# TEENSY_1.net
KiCad netlist of a schematic drawn in Altium Designer
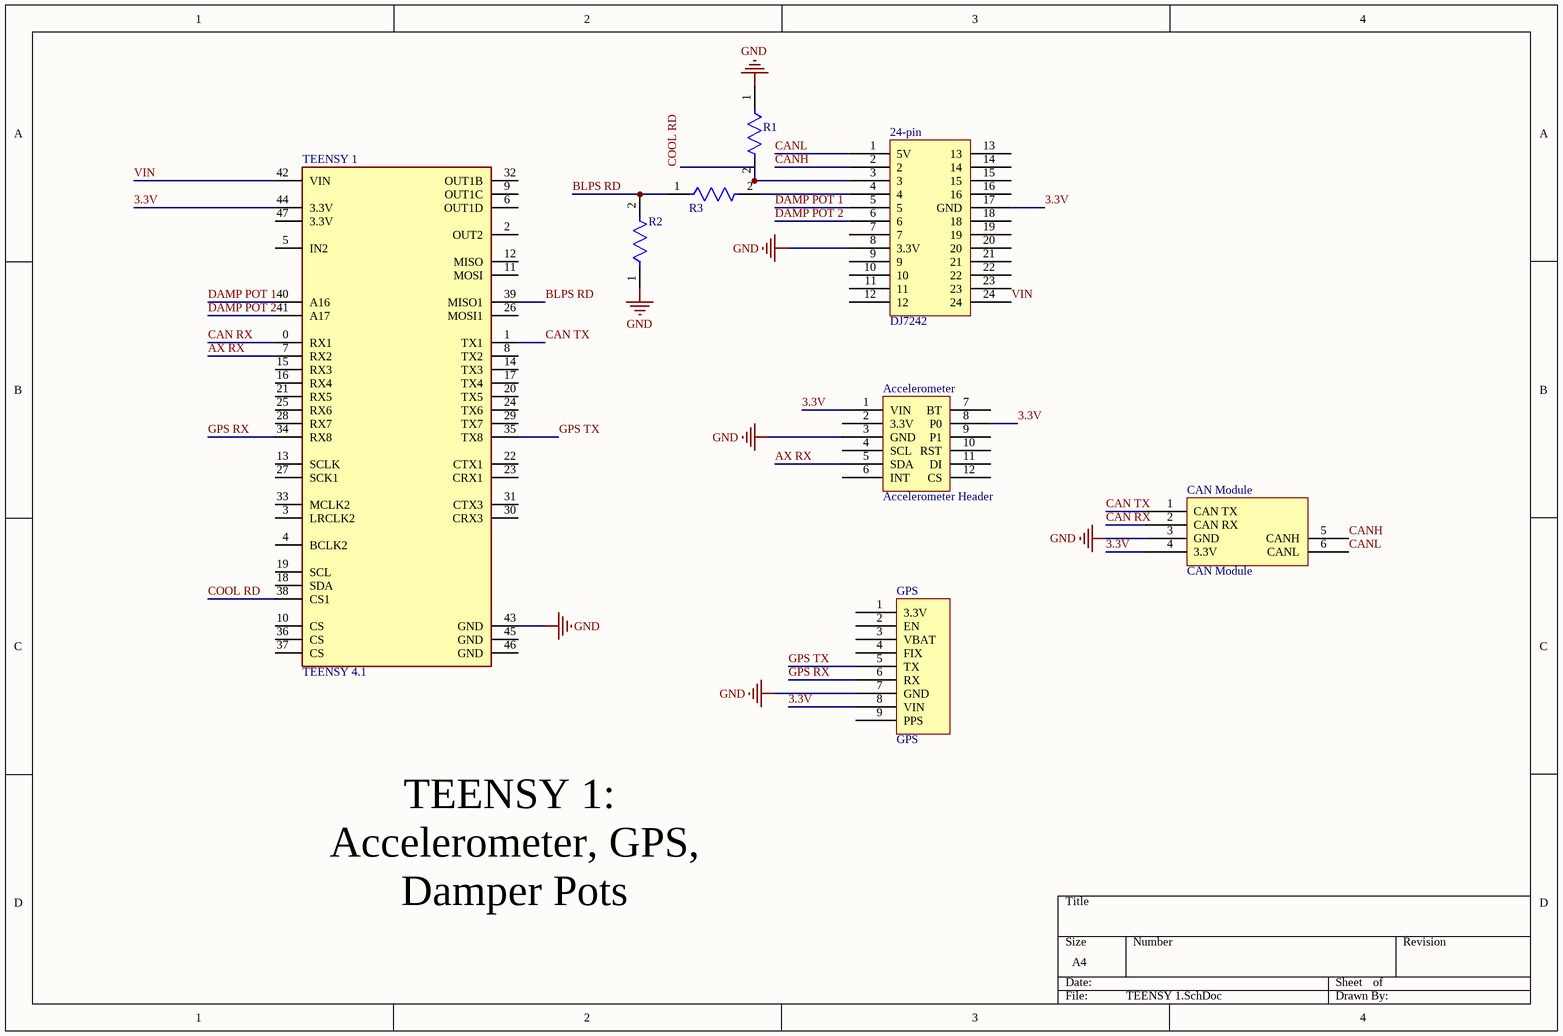
[diagram p0: TEENSY 1.SchDoc]

(export (version "E")
  (design (tool "Eeschema 10.0.6"))
  (components
    (comp (ref "24-pin")
      (value "DJ7242")
      (footprint "DJ7242-Footprint-1")
      (description "24-pin connector")
      (libsource (lib "cmabey15") (part "DJ7242-Symbol-1"))
    )
    (comp (ref "Accelerometer")
      (value "Accelerometer Header")
      (footprint "Accelerometer Header-Footprint-1")
      (description "Header for Adafruit Accelerometer")
      (libsource (lib "cmabey15") (part "Accel"))
    )
    (comp (ref "CAN Module")
      (value "CAN Module")
      (footprint "CAN Module-Footprint-1")
      (description "CAN waveshare")
      (libsource (lib "cmabey15") (part "CAN Module-Symbol-1"))
    )
    (comp (ref "GPS")
      (value "GPS")
      (footprint "GPS-Footprint-1")
      (description "Adafruit GPS chip")
      (libsource (lib "cmabey15") (part "GPS"))
    )
    (comp (ref "R1")
      (value "CMF5073K200FHEB")
      (footprint "FP-CMF50-0")
      (description "CMF5073K200FHEB Res Metal Film 73.2K Ohm 1% 0.125W(1/8W) ±50ppm/°C Epoxy AXL T/R")
      (fields (field (name "TOLERANCE") "1%"))
      (libsource (lib "Altium Content Vault") (part "1029c3af85768c4190bb7ad29bc67b5"))
    )
    (comp (ref "R2")
      (value "CMF5073K200FHEB")
      (footprint "FP-CMF50-0")
      (description "CMF5073K200FHEB Res Metal Film 73.2K Ohm 1% 0.125W(1/8W) ±50ppm/°C Epoxy AXL T/R")
      (fields (field (name "TOLERANCE") "1%"))
      (libsource (lib "Altium Content Vault") (part "1029c3af85768c4190bb7ad29bc67b5"))
    )
    (comp (ref "R3")
      (value "CMF5073K200FHEB")
      (footprint "FP-CMF50-0")
      (description "CMF5073K200FHEB Res Metal Film 73.2K Ohm 1% 0.125W(1/8W) ±50ppm/°C Epoxy AXL T/R")
      (fields (field (name "TOLERANCE") "1%"))
      (libsource (lib "Altium Content Vault") (part "1029c3af85768c4190bb7ad29bc67b5"))
    )
    (comp (ref "TEENSY 1")
      (value "TEENSY 4.1")
      (footprint "FP-DEV-16996-MFG")
      (description "TEENSY 4.1 (HEADERS)")
      (libsource (lib "Altium Content Vault") (part "080115a1ce54750370cf87ec145ee29"))
    )
  )
  (nets
    (net (code "1") (name "/3.3V") (class "Default")
      (node (ref "24-pin") (pin "17") (pinfunction "GND_17") (pintype "passive"))
      (node (ref "Accelerometer") (pin "1") (pinfunction "VIN_1") (pintype "passive"))
      (node (ref "Accelerometer") (pin "8") (pinfunction "P0_8") (pintype "passive"))
      (node (ref "CAN Module") (pin "4") (pinfunction "3.3V_4") (pintype "passive"))
      (node (ref "GPS") (pin "8") (pinfunction "VIN_8") (pintype "passive"))
      (node (ref "TEENSY 1") (pin "44") (pinfunction "3.3V_44") (pintype "passive"))
    )
    (net (code "2") (name "/AX RX") (class "Default")
      (node (ref "Accelerometer") (pin "5") (pinfunction "SDA_5") (pintype "passive"))
      (node (ref "TEENSY 1") (pin "7") (pinfunction "RX2_7") (pintype "passive"))
    )
    (net (code "3") (name "/BLPS RD") (class "Default")
      (node (ref "R2") (pin "2") (pinfunction "2_2") (pintype "passive"))
      (node (ref "R3") (pin "1") (pinfunction "1_1") (pintype "passive"))
      (node (ref "TEENSY 1") (pin "39") (pinfunction "MISO1_39") (pintype "passive"))
    )
    (net (code "4") (name "/CAN RX") (class "Default")
      (node (ref "CAN Module") (pin "2") (pinfunction "CAN_RX_2") (pintype "passive"))
      (node (ref "TEENSY 1") (pin "0") (pinfunction "RX1_0") (pintype "passive"))
    )
    (net (code "5") (name "/CAN TX") (class "Default")
      (node (ref "CAN Module") (pin "1") (pinfunction "CAN_TX_1") (pintype "passive"))
      (node (ref "TEENSY 1") (pin "1") (pinfunction "TX1_1") (pintype "passive"))
    )
    (net (code "6") (name "/CANH") (class "Default")
      (node (ref "24-pin") (pin "2") (pinfunction "2_2") (pintype "passive"))
      (node (ref "CAN Module") (pin "5") (pinfunction "CANH_5") (pintype "passive"))
    )
    (net (code "7") (name "/CANL") (class "Default")
      (node (ref "24-pin") (pin "1") (pinfunction "5V_1") (pintype "passive"))
      (node (ref "CAN Module") (pin "6") (pinfunction "CANL_6") (pintype "passive"))
    )
    (net (code "8") (name "/COOL RD") (class "Default")
      (node (ref "24-pin") (pin "3") (pinfunction "3_3") (pintype "passive"))
      (node (ref "R1") (pin "2") (pinfunction "2_2") (pintype "passive"))
      (node (ref "TEENSY 1") (pin "38") (pinfunction "CS1_38") (pintype "passive"))
    )
    (net (code "9") (name "/DAMP POT 1") (class "Default")
      (node (ref "24-pin") (pin "5") (pinfunction "5_5") (pintype "passive"))
      (node (ref "TEENSY 1") (pin "40") (pinfunction "A16_40") (pintype "passive"))
    )
    (net (code "10") (name "/DAMP POT 2") (class "Default")
      (node (ref "24-pin") (pin "6") (pinfunction "6_6") (pintype "passive"))
      (node (ref "TEENSY 1") (pin "41") (pinfunction "A17_41") (pintype "passive"))
    )
    (net (code "11") (name "/GPS RX") (class "Default")
      (node (ref "GPS") (pin "6") (pinfunction "RX_6") (pintype "passive"))
      (node (ref "TEENSY 1") (pin "34") (pinfunction "RX8_34") (pintype "passive"))
    )
    (net (code "12") (name "/GPS TX") (class "Default")
      (node (ref "GPS") (pin "5") (pinfunction "TX_5") (pintype "passive"))
      (node (ref "TEENSY 1") (pin "35") (pinfunction "TX8_35") (pintype "passive"))
    )
    (net (code "13") (name "/VIN") (class "Default")
      (node (ref "24-pin") (pin "24") (pinfunction "24_24") (pintype "passive"))
      (node (ref "TEENSY 1") (pin "42") (pinfunction "VIN_42") (pintype "passive"))
    )
    (net (code "14") (name "GND") (class "Default")
      (node (ref "24-pin") (pin "8") (pinfunction "3.3V_8") (pintype "passive"))
      (node (ref "Accelerometer") (pin "3") (pinfunction "GND_3") (pintype "passive"))
      (node (ref "CAN Module") (pin "3") (pinfunction "GND_3") (pintype "passive"))
      (node (ref "GPS") (pin "7") (pinfunction "GND_7") (pintype "passive"))
      (node (ref "R1") (pin "1") (pinfunction "1_1") (pintype "passive"))
      (node (ref "R2") (pin "1") (pinfunction "1_1") (pintype "passive"))
      (node (ref "TEENSY 1") (pin "43") (pinfunction "GND_43") (pintype "passive"))
    )
    (net (code "15") (name "Net-(24-pin-Pad4)") (class "Default")
      (node (ref "24-pin") (pin "4") (pinfunction "4_4") (pintype "passive"))
      (node (ref "R3") (pin "2") (pinfunction "2_2") (pintype "passive"))
    )
    (net (code "16") (name "unconnected-(24-pin-Pad7)") (class "Default")
      (node (ref "24-pin") (pin "7") (pinfunction "7_7") (pintype "passive"))
    )
    (net (code "17") (name "unconnected-(24-pin-Pad9)") (class "Default")
      (node (ref "24-pin") (pin "9") (pinfunction "9_9") (pintype "passive"))
    )
    (net (code "18") (name "unconnected-(24-pin-Pad10)") (class "Default")
      (node (ref "24-pin") (pin "10") (pinfunction "10_10") (pintype "passive"))
    )
    (net (code "19") (name "unconnected-(24-pin-Pad11)") (class "Default")
      (node (ref "24-pin") (pin "11") (pinfunction "11_11") (pintype "passive"))
    )
    (net (code "20") (name "unconnected-(24-pin-Pad12)") (class "Default")
      (node (ref "24-pin") (pin "12") (pinfunction "12_12") (pintype "passive"))
    )
    (net (code "21") (name "unconnected-(24-pin-Pad13)") (class "Default")
      (node (ref "24-pin") (pin "13") (pinfunction "13_13") (pintype "passive"))
    )
    (net (code "22") (name "unconnected-(24-pin-Pad14)") (class "Default")
      (node (ref "24-pin") (pin "14") (pinfunction "14_14") (pintype "passive"))
    )
    (net (code "23") (name "unconnected-(24-pin-Pad15)") (class "Default")
      (node (ref "24-pin") (pin "15") (pinfunction "15_15") (pintype "passive"))
    )
    (net (code "24") (name "unconnected-(24-pin-Pad16)") (class "Default")
      (node (ref "24-pin") (pin "16") (pinfunction "16_16") (pintype "passive"))
    )
    (net (code "25") (name "unconnected-(24-pin-Pad18)") (class "Default")
      (node (ref "24-pin") (pin "18") (pinfunction "18_18") (pintype "passive"))
    )
    (net (code "26") (name "unconnected-(24-pin-Pad19)") (class "Default")
      (node (ref "24-pin") (pin "19") (pinfunction "19_19") (pintype "passive"))
    )
    (net (code "27") (name "unconnected-(24-pin-Pad20)") (class "Default")
      (node (ref "24-pin") (pin "20") (pinfunction "20_20") (pintype "passive"))
    )
    (net (code "28") (name "unconnected-(24-pin-Pad21)") (class "Default")
      (node (ref "24-pin") (pin "21") (pinfunction "21_21") (pintype "passive"))
    )
    (net (code "29") (name "unconnected-(24-pin-Pad22)") (class "Default")
      (node (ref "24-pin") (pin "22") (pinfunction "22_22") (pintype "passive"))
    )
    (net (code "30") (name "unconnected-(24-pin-Pad23)") (class "Default")
      (node (ref "24-pin") (pin "23") (pinfunction "23_23") (pintype "passive"))
    )
    (net (code "31") (name "unconnected-(Accelerometer-3.3V-Pad2)") (class "Default")
      (node (ref "Accelerometer") (pin "2") (pinfunction "3.3V_2") (pintype "passive"))
    )
    (net (code "32") (name "unconnected-(Accelerometer-BT-Pad7)") (class "Default")
      (node (ref "Accelerometer") (pin "7") (pinfunction "BT_7") (pintype "passive"))
    )
    (net (code "33") (name "unconnected-(Accelerometer-CS-Pad12)") (class "Default")
      (node (ref "Accelerometer") (pin "12") (pinfunction "CS_12") (pintype "passive"))
    )
    (net (code "34") (name "unconnected-(Accelerometer-DI-Pad11)") (class "Default")
      (node (ref "Accelerometer") (pin "11") (pinfunction "DI_11") (pintype "passive"))
    )
    (net (code "35") (name "unconnected-(Accelerometer-INT-Pad6)") (class "Default")
      (node (ref "Accelerometer") (pin "6") (pinfunction "INT_6") (pintype "passive"))
    )
    (net (code "36") (name "unconnected-(Accelerometer-P1-Pad9)") (class "Default")
      (node (ref "Accelerometer") (pin "9") (pinfunction "P1_9") (pintype "passive"))
    )
    (net (code "37") (name "unconnected-(Accelerometer-RST-Pad10)") (class "Default")
      (node (ref "Accelerometer") (pin "10") (pinfunction "RST_10") (pintype "passive"))
    )
    (net (code "38") (name "unconnected-(Accelerometer-SCL-Pad4)") (class "Default")
      (node (ref "Accelerometer") (pin "4") (pinfunction "SCL_4") (pintype "passive"))
    )
    (net (code "39") (name "unconnected-(GPS-3.3V-Pad1)") (class "Default")
      (node (ref "GPS") (pin "1") (pinfunction "3.3V_1") (pintype "passive"))
    )
    (net (code "40") (name "unconnected-(GPS-EN-Pad2)") (class "Default")
      (node (ref "GPS") (pin "2") (pinfunction "EN_2") (pintype "passive"))
    )
    (net (code "41") (name "unconnected-(GPS-FIX-Pad4)") (class "Default")
      (node (ref "GPS") (pin "4") (pinfunction "FIX_4") (pintype "passive"))
    )
    (net (code "42") (name "unconnected-(GPS-PPS-Pad9)") (class "Default")
      (node (ref "GPS") (pin "9") (pinfunction "PPS_9") (pintype "passive"))
    )
    (net (code "43") (name "unconnected-(GPS-VBAT-Pad3)") (class "Default")
      (node (ref "GPS") (pin "3") (pinfunction "VBAT_3") (pintype "passive"))
    )
    (net (code "44") (name "unconnected-(TEENSY 1-3.3V-Pad47)") (class "Default")
      (node (ref "TEENSY 1") (pin "47") (pinfunction "3.3V_47") (pintype "passive"))
    )
    (net (code "45") (name "unconnected-(TEENSY 1-BCLK2-Pad4)") (class "Default")
      (node (ref "TEENSY 1") (pin "4") (pinfunction "BCLK2_4") (pintype "passive"))
    )
    (net (code "46") (name "unconnected-(TEENSY 1-CRX1-Pad23)") (class "Default")
      (node (ref "TEENSY 1") (pin "23") (pinfunction "CRX1_23") (pintype "passive"))
    )
    (net (code "47") (name "unconnected-(TEENSY 1-CRX3-Pad30)") (class "Default")
      (node (ref "TEENSY 1") (pin "30") (pinfunction "CRX3_30") (pintype "passive"))
    )
    (net (code "48") (name "unconnected-(TEENSY 1-CS-Pad10)") (class "Default")
      (node (ref "TEENSY 1") (pin "10") (pinfunction "CS_10") (pintype "passive"))
    )
    (net (code "49") (name "unconnected-(TEENSY 1-CS-Pad36)") (class "Default")
      (node (ref "TEENSY 1") (pin "36") (pinfunction "CS_36") (pintype "passive"))
    )
    (net (code "50") (name "unconnected-(TEENSY 1-CS-Pad37)") (class "Default")
      (node (ref "TEENSY 1") (pin "37") (pinfunction "CS_37") (pintype "passive"))
    )
    (net (code "51") (name "unconnected-(TEENSY 1-CTX1-Pad22)") (class "Default")
      (node (ref "TEENSY 1") (pin "22") (pinfunction "CTX1_22") (pintype "passive"))
    )
    (net (code "52") (name "unconnected-(TEENSY 1-CTX3-Pad31)") (class "Default")
      (node (ref "TEENSY 1") (pin "31") (pinfunction "CTX3_31") (pintype "passive"))
    )
    (net (code "53") (name "unconnected-(TEENSY 1-GND-Pad45)") (class "Default")
      (node (ref "TEENSY 1") (pin "45") (pinfunction "GND_45") (pintype "passive"))
    )
    (net (code "54") (name "unconnected-(TEENSY 1-GND-Pad46)") (class "Default")
      (node (ref "TEENSY 1") (pin "46") (pinfunction "GND_46") (pintype "passive"))
    )
    (net (code "55") (name "unconnected-(TEENSY 1-IN2-Pad5)") (class "Default")
      (node (ref "TEENSY 1") (pin "5") (pinfunction "IN2_5") (pintype "passive"))
    )
    (net (code "56") (name "unconnected-(TEENSY 1-LRCLK2-Pad3)") (class "Default")
      (node (ref "TEENSY 1") (pin "3") (pinfunction "LRCLK2_3") (pintype "passive"))
    )
    (net (code "57") (name "unconnected-(TEENSY 1-MCLK2-Pad33)") (class "Default")
      (node (ref "TEENSY 1") (pin "33") (pinfunction "MCLK2_33") (pintype "passive"))
    )
    (net (code "58") (name "unconnected-(TEENSY 1-MISO-Pad12)") (class "Default")
      (node (ref "TEENSY 1") (pin "12") (pinfunction "MISO_12") (pintype "passive"))
    )
    (net (code "59") (name "unconnected-(TEENSY 1-MOSI-Pad11)") (class "Default")
      (node (ref "TEENSY 1") (pin "11") (pinfunction "MOSI_11") (pintype "passive"))
    )
    (net (code "60") (name "unconnected-(TEENSY 1-MOSI1-Pad26)") (class "Default")
      (node (ref "TEENSY 1") (pin "26") (pinfunction "MOSI1_26") (pintype "passive"))
    )
    (net (code "61") (name "unconnected-(TEENSY 1-OUT1B-Pad32)") (class "Default")
      (node (ref "TEENSY 1") (pin "32") (pinfunction "OUT1B_32") (pintype "passive"))
    )
    (net (code "62") (name "unconnected-(TEENSY 1-OUT1C-Pad9)") (class "Default")
      (node (ref "TEENSY 1") (pin "9") (pinfunction "OUT1C_9") (pintype "passive"))
    )
    (net (code "63") (name "unconnected-(TEENSY 1-OUT1D-Pad6)") (class "Default")
      (node (ref "TEENSY 1") (pin "6") (pinfunction "OUT1D_6") (pintype "passive"))
    )
    (net (code "64") (name "unconnected-(TEENSY 1-OUT2-Pad2)") (class "Default")
      (node (ref "TEENSY 1") (pin "2") (pinfunction "OUT2_2") (pintype "passive"))
    )
    (net (code "65") (name "unconnected-(TEENSY 1-RX3-Pad15)") (class "Default")
      (node (ref "TEENSY 1") (pin "15") (pinfunction "RX3_15") (pintype "passive"))
    )
    (net (code "66") (name "unconnected-(TEENSY 1-RX4-Pad16)") (class "Default")
      (node (ref "TEENSY 1") (pin "16") (pinfunction "RX4_16") (pintype "passive"))
    )
    (net (code "67") (name "unconnected-(TEENSY 1-RX5-Pad21)") (class "Default")
      (node (ref "TEENSY 1") (pin "21") (pinfunction "RX5_21") (pintype "passive"))
    )
    (net (code "68") (name "unconnected-(TEENSY 1-RX6-Pad25)") (class "Default")
      (node (ref "TEENSY 1") (pin "25") (pinfunction "RX6_25") (pintype "passive"))
    )
    (net (code "69") (name "unconnected-(TEENSY 1-RX7-Pad28)") (class "Default")
      (node (ref "TEENSY 1") (pin "28") (pinfunction "RX7_28") (pintype "passive"))
    )
    (net (code "70") (name "unconnected-(TEENSY 1-SCK1-Pad27)") (class "Default")
      (node (ref "TEENSY 1") (pin "27") (pinfunction "SCK1_27") (pintype "passive"))
    )
    (net (code "71") (name "unconnected-(TEENSY 1-SCL-Pad19)") (class "Default")
      (node (ref "TEENSY 1") (pin "19") (pinfunction "SCL_19") (pintype "passive"))
    )
    (net (code "72") (name "unconnected-(TEENSY 1-SCLK-Pad13)") (class "Default")
      (node (ref "TEENSY 1") (pin "13") (pinfunction "SCLK_13") (pintype "passive"))
    )
    (net (code "73") (name "unconnected-(TEENSY 1-SDA-Pad18)") (class "Default")
      (node (ref "TEENSY 1") (pin "18") (pinfunction "SDA_18") (pintype "passive"))
    )
    (net (code "74") (name "unconnected-(TEENSY 1-TX2-Pad8)") (class "Default")
      (node (ref "TEENSY 1") (pin "8") (pinfunction "TX2_8") (pintype "passive"))
    )
    (net (code "75") (name "unconnected-(TEENSY 1-TX3-Pad14)") (class "Default")
      (node (ref "TEENSY 1") (pin "14") (pinfunction "TX3_14") (pintype "passive"))
    )
    (net (code "76") (name "unconnected-(TEENSY 1-TX4-Pad17)") (class "Default")
      (node (ref "TEENSY 1") (pin "17") (pinfunction "TX4_17") (pintype "passive"))
    )
    (net (code "77") (name "unconnected-(TEENSY 1-TX5-Pad20)") (class "Default")
      (node (ref "TEENSY 1") (pin "20") (pinfunction "TX5_20") (pintype "passive"))
    )
    (net (code "78") (name "unconnected-(TEENSY 1-TX6-Pad24)") (class "Default")
      (node (ref "TEENSY 1") (pin "24") (pinfunction "TX6_24") (pintype "passive"))
    )
    (net (code "79") (name "unconnected-(TEENSY 1-TX7-Pad29)") (class "Default")
      (node (ref "TEENSY 1") (pin "29") (pinfunction "TX7_29") (pintype "passive"))
    )
  )
)
